# bolid-rs485-usb-sd.net
KiCad netlist of a schematic drawn in Altium Designer
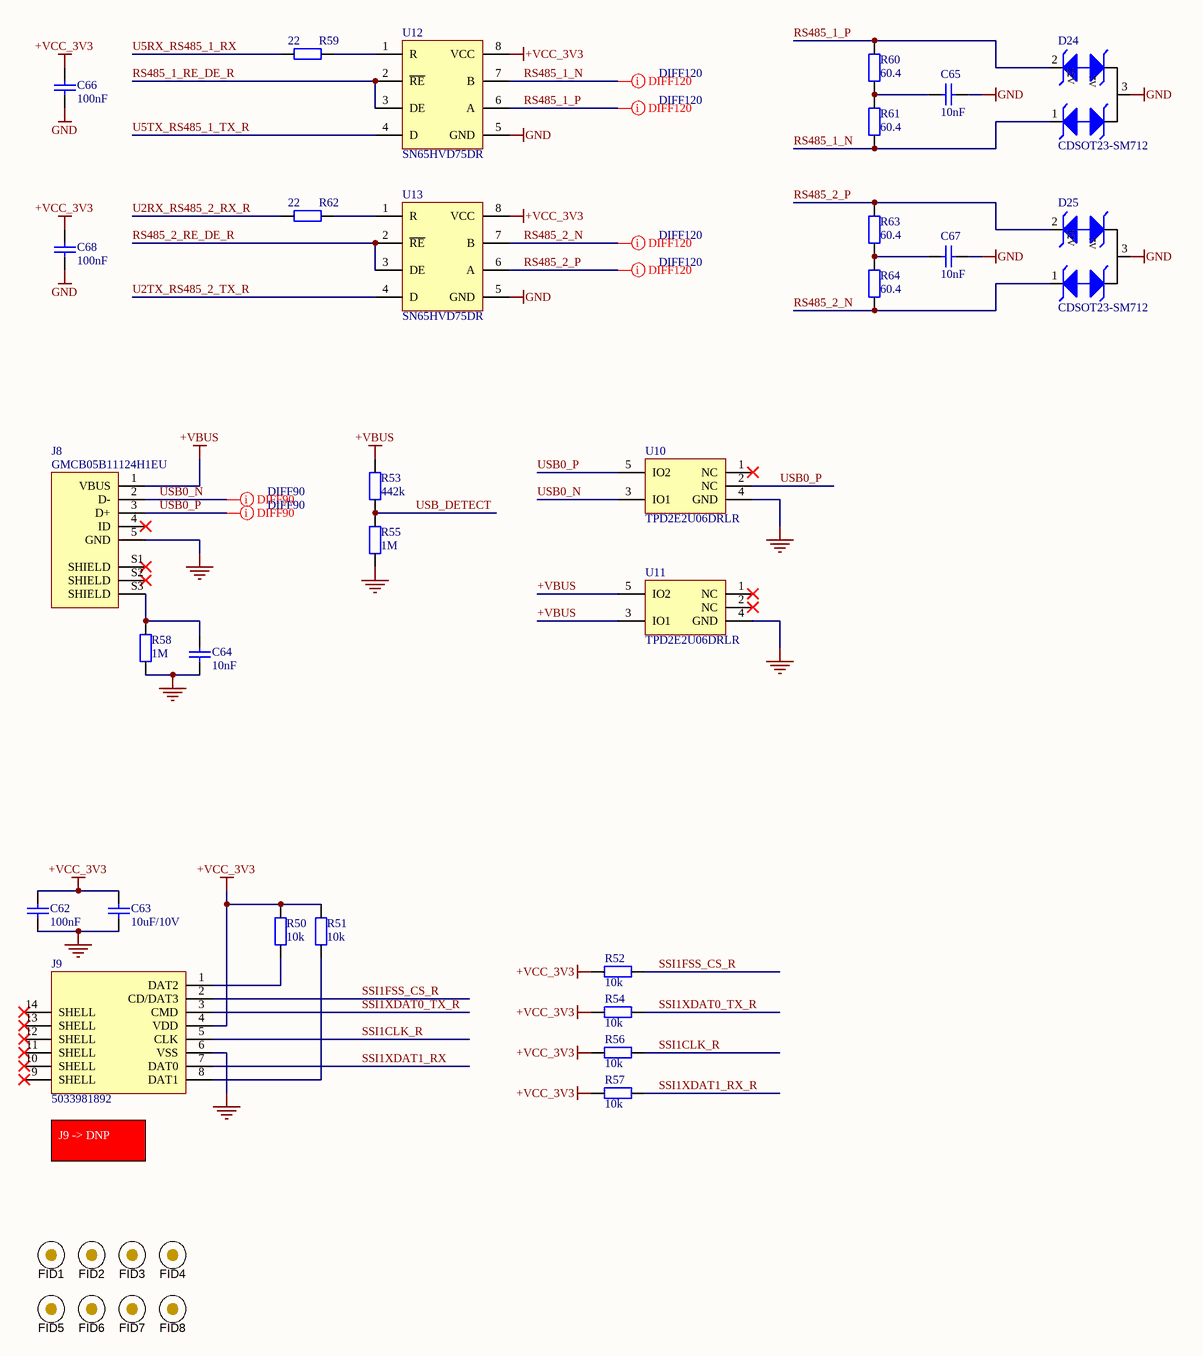
[diagram p0: bolid-rs485-usb-sd.SchDoc]

(export (version "E")
  (design (tool "Eeschema 10.0.6"))
  (components
    (comp (ref "C62")
      (value "GRM155R71H104KE14D")
      (footprint "C0402-CAPC100X50X55L22 - Tayio Yuden TDK")
      (description "MLCC 0402 (1005) 100nF 10% 50V X7R")
      (fields
        (field (name "MANUFACTURER") "Murata Electronics")
        (field (name "TOLERANCE") "10 %")
        (field (name "VALUE DISPLAYED") "100nF")
      )
      (libsource (lib "capacitors2") (part "GRM155R71H104KE14D"))
    )
    (comp (ref "C63")
      (value "GRM21BR71A106KA73K")
      (footprint "C0805-CAPC200X125X135L50N - Taiyo YudenN")
      (description "MLCC 0805 (2012) 10uF 10% 10V X7R")
      (fields
        (field (name "MANUFACTURER") "Murata Electronics")
        (field (name "TOLERANCE") "10 %")
        (field (name "VALUE DISPLAYED") "10uF/10V")
      )
      (libsource (lib "capacitors2") (part "GRM21BR71A106KA73K"))
    )
    (comp (ref "C64")
      (value "GCM155R71H103KA55D")
      (footprint "C0402-CAPC100X50X55L22 - Tayio Yuden TDK")
      (description "MLCC 0402 (1005) 10nF 10% 50V X7R")
      (fields
        (field (name "MANUFACTURER") "Murata Electronics")
        (field (name "TOLERANCE") "10 %")
        (field (name "VALUE DISPLAYED") "10nF")
      )
      (libsource (lib "capacitors2") (part "GCM155R71H103KA55D"))
    )
    (comp (ref "C65")
      (value "GCM155R71H103KA55D")
      (footprint "C0402-CAPC100X50X55L22 - Tayio Yuden TDK")
      (description "MLCC 0402 (1005) 10nF 10% 50V X7R")
      (fields
        (field (name "MANUFACTURER") "Murata Electronics")
        (field (name "TOLERANCE") "10 %")
        (field (name "VALUE DISPLAYED") "10nF")
      )
      (libsource (lib "capacitors2") (part "GCM155R71H103KA55D"))
    )
    (comp (ref "C66")
      (value "GRM155R71H104KE14D")
      (footprint "C0402-CAPC100X50X55L22 - Tayio Yuden TDK")
      (description "MLCC 0402 (1005) 100nF 10% 50V X7R")
      (fields
        (field (name "MANUFACTURER") "Murata Electronics")
        (field (name "TOLERANCE") "10 %")
        (field (name "VALUE DISPLAYED") "100nF")
      )
      (libsource (lib "capacitors2") (part "GRM155R71H104KE14D"))
    )
    (comp (ref "C67")
      (value "GCM155R71H103KA55D")
      (footprint "C0402-CAPC100X50X55L22 - Tayio Yuden TDK")
      (description "MLCC 0402 (1005) 10nF 10% 50V X7R")
      (fields
        (field (name "MANUFACTURER") "Murata Electronics")
        (field (name "TOLERANCE") "10 %")
        (field (name "VALUE DISPLAYED") "10nF")
      )
      (libsource (lib "capacitors2") (part "GCM155R71H103KA55D"))
    )
    (comp (ref "C68")
      (value "GRM155R71H104KE14D")
      (footprint "C0402-CAPC100X50X55L22 - Tayio Yuden TDK")
      (description "MLCC 0402 (1005) 100nF 10% 50V X7R")
      (fields
        (field (name "MANUFACTURER") "Murata Electronics")
        (field (name "TOLERANCE") "10 %")
        (field (name "VALUE DISPLAYED") "100nF")
      )
      (libsource (lib "capacitors2") (part "GRM155R71H104KE14D"))
    )
    (comp (ref "D24")
      (value "CDSOT23-SM712")
      (footprint "Bourns SOT-23-3L SOT23-3P95_229X117L49X40N")
      (description "TVS DIODE 7VWM/12VWM SOT23")
      (fields (field (name "MANUFACTURER") "Bourns"))
      (libsource (lib "semiconductors2") (part "CDSOT23-SM712"))
    )
    (comp (ref "D25")
      (value "CDSOT23-SM712")
      (footprint "Bourns SOT-23-3L SOT23-3P95_229X117L49X40N")
      (description "TVS DIODE 7VWM/12VWM SOT23")
      (fields (field (name "MANUFACTURER") "Bourns"))
      (libsource (lib "semiconductors2") (part "CDSOT23-SM712"))
    )
    (comp (ref "FID1")
      (value "Fiducial")
      (footprint "Fiducial10-20")
      (description "Fiducial mark on PCB")
      (libsource (lib "hardware2") (part "Fiducial"))
    )
    (comp (ref "FID2")
      (value "Fiducial")
      (footprint "Fiducial10-20")
      (description "Fiducial mark on PCB")
      (libsource (lib "hardware2") (part "Fiducial"))
    )
    (comp (ref "FID3")
      (value "Fiducial")
      (footprint "Fiducial10-20")
      (description "Fiducial mark on PCB")
      (libsource (lib "hardware2") (part "Fiducial"))
    )
    (comp (ref "FID4")
      (value "Fiducial")
      (footprint "Fiducial10-20")
      (description "Fiducial mark on PCB")
      (libsource (lib "hardware2") (part "Fiducial"))
    )
    (comp (ref "FID5")
      (value "Fiducial")
      (footprint "Fiducial10-20")
      (description "Fiducial mark on PCB")
      (libsource (lib "hardware2") (part "Fiducial"))
    )
    (comp (ref "FID6")
      (value "Fiducial")
      (footprint "Fiducial10-20")
      (description "Fiducial mark on PCB")
      (libsource (lib "hardware2") (part "Fiducial"))
    )
    (comp (ref "FID7")
      (value "Fiducial")
      (footprint "Fiducial10-20")
      (description "Fiducial mark on PCB")
      (libsource (lib "hardware2") (part "Fiducial"))
    )
    (comp (ref "FID8")
      (value "Fiducial")
      (footprint "Fiducial10-20")
      (description "Fiducial mark on PCB")
      (libsource (lib "hardware2") (part "Fiducial"))
    )
    (comp (ref "J8")
      (value "GMCB05B11124H1EU")
      (footprint "AMPHENOL-GMCB05B11124H1EU")
      (description "Micro USB 2.0 Type B Receptacle Vertical SMT Shell Dip Length 1.7mm, Tape and Reel Packagin")
      (fields (field (name "MANUFACTURER") "Amphenol"))
      (libsource (lib "connectors2") (part "GMCB05B11124H1EU"))
    )
    (comp (ref "J9")
      (value "5033981892")
      (footprint "MOLEX MICROSD 5033981892")
      (fields (field (name "MANUFACTURER") "Molex"))
      (libsource (lib "connectors2") (part "5033981892"))
    )
    (comp (ref "R50")
      (value "10k")
      (footprint "R0402-RESC100X50X40L22N")
      (description "RES 0402 (1005) 10.0k 1% 0.0625W 50V Thick Film")
      (fields
        (field (name "MANUFACTURER") "Yageo")
        (field (name "MANUFACTURER PART NUMBER") "RC0402FR-0710KL")
      )
      (libsource (lib "") (part "RC0402FR-0710KL_1"))
    )
    (comp (ref "R51")
      (value "10k")
      (footprint "R0402-RESC100X50X40L22N")
      (description "RES 0402 (1005) 10.0k 1% 0.0625W 50V Thick Film")
      (fields
        (field (name "MANUFACTURER") "Yageo")
        (field (name "MANUFACTURER PART NUMBER") "RC0402FR-0710KL")
      )
      (libsource (lib "") (part "RC0402FR-0710KL_1"))
    )
    (comp (ref "R52")
      (value "10k")
      (footprint "R0402-RESC100X50X40L22N")
      (description "RES 0402 (1005) 10.0k 1% 0.0625W 50V Thick Film")
      (fields
        (field (name "MANUFACTURER") "Yageo")
        (field (name "MANUFACTURER PART NUMBER") "RC0402FR-0710KL")
      )
      (libsource (lib "resistors2") (part "RC0402FR-0710KL"))
    )
    (comp (ref "R53")
      (value "442k")
      (footprint "R0402-RESC100X50X40L22N")
      (description "RES 0402 (1005) 442.0k 1% 0.100W 50V Thick Film")
      (fields
        (field (name "MANUFACTURER") "Panasonic")
        (field (name "MANUFACTURER PART NUMBER") "ERJ-2RKF4423X")
      )
      (libsource (lib "resistors2") (part "ERJ-2RKF4423X"))
    )
    (comp (ref "R54")
      (value "10k")
      (footprint "R0402-RESC100X50X40L22N")
      (description "RES 0402 (1005) 10.0k 1% 0.0625W 50V Thick Film")
      (fields
        (field (name "MANUFACTURER") "Yageo")
        (field (name "MANUFACTURER PART NUMBER") "RC0402FR-0710KL")
      )
      (libsource (lib "resistors2") (part "RC0402FR-0710KL"))
    )
    (comp (ref "R55")
      (value "1M")
      (footprint "R0402-RESC100X50X40L22N")
      (description "RES 0402 (1005) 1.00M 1% 0.0625W 50V Thick Film")
      (fields
        (field (name "MANUFACTURER") "YAGEO")
        (field (name "MANUFACTURER PART NUMBER") "AC0402FR-071ML")
      )
      (libsource (lib "resistors2") (part "AC0402FR-071ML"))
    )
    (comp (ref "R56")
      (value "10k")
      (footprint "R0402-RESC100X50X40L22N")
      (description "RES 0402 (1005) 10.0k 1% 0.0625W 50V Thick Film")
      (fields
        (field (name "MANUFACTURER") "Yageo")
        (field (name "MANUFACTURER PART NUMBER") "RC0402FR-0710KL")
      )
      (libsource (lib "resistors2") (part "RC0402FR-0710KL"))
    )
    (comp (ref "R57")
      (value "10k")
      (footprint "R0402-RESC100X50X40L22N")
      (description "RES 0402 (1005) 10.0k 1% 0.0625W 50V Thick Film")
      (fields
        (field (name "MANUFACTURER") "Yageo")
        (field (name "MANUFACTURER PART NUMBER") "RC0402FR-0710KL")
      )
      (libsource (lib "resistors2") (part "RC0402FR-0710KL"))
    )
    (comp (ref "R58")
      (value "1M")
      (footprint "R0402-RESC100X50X40L22N")
      (description "RES 0402 (1005) 1.00M 1% 0.0625W 50V Thick Film")
      (fields
        (field (name "MANUFACTURER") "YAGEO")
        (field (name "MANUFACTURER PART NUMBER") "AC0402FR-071ML")
      )
      (libsource (lib "resistors2") (part "AC0402FR-071ML"))
    )
    (comp (ref "R59")
      (value "22")
      (footprint "R0402-RESC100X50X40L22N")
      (description "RES 0402 (1005) 22.0 ohm 1% 0.0625W 50V Thick Film")
      (fields
        (field (name "MANUFACTURER") "Yageo")
        (field (name "MANUFACTURER PART NUMBER") "RC0402FR-1322RL")
      )
      (libsource (lib "resistors2") (part "RC0402FR-1322RL"))
    )
    (comp (ref "R60")
      (value "60.4")
      (footprint "R0603-RESC160X80X55L30N")
      (description "RES 0603 (1608) 60.4 ohm 1% 0.100W 75V Thick Film")
      (fields
        (field (name "MANUFACTURER") "Yageo")
        (field (name "MANUFACTURER PART NUMBER") "RC0603FR-0760R4L")
      )
      (libsource (lib "resistors2") (part "RC0603FR-0760R4L"))
    )
    (comp (ref "R61")
      (value "60.4")
      (footprint "R0603-RESC160X80X55L30N")
      (description "RES 0603 (1608) 60.4 ohm 1% 0.100W 75V Thick Film")
      (fields
        (field (name "MANUFACTURER") "Yageo")
        (field (name "MANUFACTURER PART NUMBER") "RC0603FR-0760R4L")
      )
      (libsource (lib "resistors2") (part "RC0603FR-0760R4L"))
    )
    (comp (ref "R62")
      (value "22")
      (footprint "R0402-RESC100X50X40L22N")
      (description "RES 0402 (1005) 22.0 ohm 1% 0.0625W 50V Thick Film")
      (fields
        (field (name "MANUFACTURER") "Yageo")
        (field (name "MANUFACTURER PART NUMBER") "RC0402FR-1322RL")
      )
      (libsource (lib "resistors2") (part "RC0402FR-1322RL"))
    )
    (comp (ref "R63")
      (value "60.4")
      (footprint "R0603-RESC160X80X55L30N")
      (description "RES 0603 (1608) 60.4 ohm 1% 0.100W 75V Thick Film")
      (fields
        (field (name "MANUFACTURER") "Yageo")
        (field (name "MANUFACTURER PART NUMBER") "RC0603FR-0760R4L")
      )
      (libsource (lib "resistors2") (part "RC0603FR-0760R4L"))
    )
    (comp (ref "R64")
      (value "60.4")
      (footprint "R0603-RESC160X80X55L30N")
      (description "RES 0603 (1608) 60.4 ohm 1% 0.100W 75V Thick Film")
      (fields
        (field (name "MANUFACTURER") "Yageo")
        (field (name "MANUFACTURER PART NUMBER") "RC0603FR-0760R4L")
      )
      (libsource (lib "resistors2") (part "RC0603FR-0760R4L"))
    )
    (comp (ref "U10")
      (value "TPD2E2U06DRLR")
      (footprint "TI SOT-5X3 DRL0005A SOTFL50P160X60-5N")
      (description "TVS DIODE 5.5VWM 12.4VC 5SOT")
      (fields (field (name "MANUFACTURER") "Texas Instruments"))
      (libsource (lib "semiconductors2") (part "TPD2E2U06DRLR"))
    )
    (comp (ref "U11")
      (value "TPD2E2U06DRLR")
      (footprint "TI SOT-5X3 DRL0005A SOTFL50P160X60-5N")
      (description "TVS DIODE 5.5VWM 12.4VC 5SOT")
      (fields (field (name "MANUFACTURER") "Texas Instruments"))
      (libsource (lib "semiconductors2") (part "TPD2E2U06DRLR"))
    )
    (comp (ref "U12")
      (value "SN65HVD75DR")
      (footprint "TI SOIC8 D0008A SOIC8P127_490X599X175L84X41N")
      (description "IC TXRX RS485 3.3V LP 8SOIC")
      (fields (field (name "MANUFACTURER") "Texas Instruments"))
      (libsource (lib "ics2") (part "SN65HVD75DR"))
    )
    (comp (ref "U13")
      (value "SN65HVD75DR")
      (footprint "TI SOIC8 D0008A SOIC8P127_490X599X175L84X41N")
      (description "IC TXRX RS485 3.3V LP 8SOIC")
      (fields (field (name "MANUFACTURER") "Texas Instruments"))
      (libsource (lib "ics2") (part "SN65HVD75DR"))
    )
  )
  (nets
    (net (code "1") (name "+VBUS") (class "Default")
      (node (ref "J8") (pin "1") (pinfunction "VBUS_1") (pintype "power_in"))
      (node (ref "R53") (pin "2") (pinfunction "2_2") (pintype "passive"))
      (node (ref "U11") (pin "3") (pinfunction "IO1_3") (pintype "passive"))
      (node (ref "U11") (pin "5") (pinfunction "IO2_5") (pintype "passive"))
    )
    (net (code "2") (name "+VCC_3V3") (class "Default")
      (node (ref "C62") (pin "2") (pinfunction "2_2") (pintype "passive"))
      (node (ref "C63") (pin "1") (pinfunction "1_1") (pintype "passive"))
      (node (ref "C66") (pin "1") (pinfunction "1_1") (pintype "passive"))
      (node (ref "C68") (pin "1") (pinfunction "1_1") (pintype "passive"))
      (node (ref "J9") (pin "4") (pinfunction "VDD_4") (pintype "passive"))
      (node (ref "R50") (pin "1") (pinfunction "1_1") (pintype "passive"))
      (node (ref "R51") (pin "1") (pinfunction "1_1") (pintype "passive"))
      (node (ref "R52") (pin "1") (pinfunction "1_1") (pintype "passive"))
      (node (ref "R54") (pin "1") (pinfunction "1_1") (pintype "passive"))
      (node (ref "R56") (pin "1") (pinfunction "1_1") (pintype "passive"))
      (node (ref "R57") (pin "1") (pinfunction "1_1") (pintype "passive"))
      (node (ref "U12") (pin "8") (pinfunction "VCC_8") (pintype "passive"))
      (node (ref "U13") (pin "8") (pinfunction "VCC_8") (pintype "passive"))
    )
    (net (code "3") (name "/RS485_1_N") (class "Default")
      (node (ref "D24") (pin "1") (pinfunction "1_1") (pintype "passive"))
      (node (ref "R61") (pin "1") (pinfunction "1_1") (pintype "passive"))
      (node (ref "U12") (pin "7") (pinfunction "B_7") (pintype "passive"))
    )
    (net (code "4") (name "/RS485_1_P") (class "Default")
      (node (ref "D24") (pin "2") (pinfunction "2_2") (pintype "passive"))
      (node (ref "R60") (pin "2") (pinfunction "2_2") (pintype "passive"))
      (node (ref "U12") (pin "6") (pinfunction "A_6") (pintype "passive"))
    )
    (net (code "5") (name "/RS485_1_RE_DE_R") (class "Default")
      (node (ref "U12") (pin "2") (pinfunction "~{RE}_2") (pintype "passive"))
      (node (ref "U12") (pin "3") (pinfunction "DE_3") (pintype "passive"))
    )
    (net (code "6") (name "/RS485_2_N") (class "Default")
      (node (ref "D25") (pin "1") (pinfunction "1_1") (pintype "passive"))
      (node (ref "R64") (pin "1") (pinfunction "1_1") (pintype "passive"))
      (node (ref "U13") (pin "7") (pinfunction "B_7") (pintype "passive"))
    )
    (net (code "7") (name "/RS485_2_P") (class "Default")
      (node (ref "D25") (pin "2") (pinfunction "2_2") (pintype "passive"))
      (node (ref "R63") (pin "2") (pinfunction "2_2") (pintype "passive"))
      (node (ref "U13") (pin "6") (pinfunction "A_6") (pintype "passive"))
    )
    (net (code "8") (name "/RS485_2_RE_DE_R") (class "Default")
      (node (ref "U13") (pin "2") (pinfunction "~{RE}_2") (pintype "passive"))
      (node (ref "U13") (pin "3") (pinfunction "DE_3") (pintype "passive"))
    )
    (net (code "9") (name "/SSI1CLK_R") (class "Default")
      (node (ref "J9") (pin "5") (pinfunction "CLK_5") (pintype "passive"))
      (node (ref "R56") (pin "2") (pinfunction "2_2") (pintype "passive"))
    )
    (net (code "10") (name "/SSI1FSS_CS_R") (class "Default")
      (node (ref "J9") (pin "2") (pinfunction "CD/DAT3_2") (pintype "passive"))
      (node (ref "R52") (pin "2") (pinfunction "2_2") (pintype "passive"))
    )
    (net (code "11") (name "/SSI1XDAT0_TX_R") (class "Default")
      (node (ref "J9") (pin "3") (pinfunction "CMD_3") (pintype "passive"))
      (node (ref "R54") (pin "2") (pinfunction "2_2") (pintype "passive"))
    )
    (net (code "12") (name "/SSI1XDAT1_RX") (class "Default")
      (node (ref "J9") (pin "7") (pinfunction "DAT0_7") (pintype "passive"))
    )
    (net (code "13") (name "/SSI1XDAT1_RX_R") (class "Default")
      (node (ref "R57") (pin "2") (pinfunction "2_2") (pintype "passive"))
    )
    (net (code "14") (name "/U2RX_RS485_2_RX_R") (class "Default")
      (node (ref "R62") (pin "1") (pinfunction "1_1") (pintype "passive"))
    )
    (net (code "15") (name "/U2TX_RS485_2_TX_R") (class "Default")
      (node (ref "U13") (pin "4") (pinfunction "D_4") (pintype "passive"))
    )
    (net (code "16") (name "/U5RX_RS485_1_RX") (class "Default")
      (node (ref "R59") (pin "1") (pinfunction "1_1") (pintype "passive"))
    )
    (net (code "17") (name "/U5TX_RS485_1_TX_R") (class "Default")
      (node (ref "U12") (pin "4") (pinfunction "D_4") (pintype "passive"))
    )
    (net (code "18") (name "/USB0_N") (class "Default")
      (node (ref "J8") (pin "2") (pinfunction "D-_2") (pintype "passive"))
      (node (ref "U10") (pin "3") (pinfunction "IO1_3") (pintype "passive"))
    )
    (net (code "19") (name "/USB0_P") (class "Default")
      (node (ref "J8") (pin "3") (pinfunction "D+_3") (pintype "passive"))
      (node (ref "U10") (pin "2") (pinfunction "NC_2") (pintype "passive"))
      (node (ref "U10") (pin "5") (pinfunction "IO2_5") (pintype "passive"))
    )
    (net (code "20") (name "/USB_DETECT") (class "Default")
      (node (ref "R53") (pin "1") (pinfunction "1_1") (pintype "passive"))
      (node (ref "R55") (pin "2") (pinfunction "2_2") (pintype "passive"))
    )
    (net (code "21") (name "GND") (class "Default")
      (node (ref "C62") (pin "1") (pinfunction "1_1") (pintype "passive"))
      (node (ref "C63") (pin "2") (pinfunction "2_2") (pintype "passive"))
      (node (ref "C64") (pin "1") (pinfunction "1_1") (pintype "passive"))
      (node (ref "C65") (pin "2") (pinfunction "2_2") (pintype "passive"))
      (node (ref "C66") (pin "2") (pinfunction "2_2") (pintype "passive"))
      (node (ref "C67") (pin "2") (pinfunction "2_2") (pintype "passive"))
      (node (ref "C68") (pin "2") (pinfunction "2_2") (pintype "passive"))
      (node (ref "D24") (pin "3") (pinfunction "3_3") (pintype "passive"))
      (node (ref "D25") (pin "3") (pinfunction "3_3") (pintype "passive"))
      (node (ref "J8") (pin "5") (pinfunction "GND_5") (pintype "power_in"))
      (node (ref "J9") (pin "6") (pinfunction "VSS_6") (pintype "passive"))
      (node (ref "R55") (pin "1") (pinfunction "1_1") (pintype "passive"))
      (node (ref "R58") (pin "1") (pinfunction "1_1") (pintype "passive"))
      (node (ref "U10") (pin "4") (pinfunction "GND_4") (pintype "passive"))
      (node (ref "U11") (pin "4") (pinfunction "GND_4") (pintype "passive"))
      (node (ref "U12") (pin "5") (pinfunction "GND_5") (pintype "passive"))
      (node (ref "U13") (pin "5") (pinfunction "GND_5") (pintype "passive"))
    )
    (net (code "22") (name "Net-(C64-Pad2)") (class "Default")
      (node (ref "C64") (pin "2") (pinfunction "2_2") (pintype "passive"))
      (node (ref "J8") (pin "S3") (pinfunction "SHIELD_S3") (pintype "passive"))
      (node (ref "R58") (pin "2") (pinfunction "2_2") (pintype "passive"))
    )
    (net (code "23") (name "Net-(C65-Pad1)") (class "Default")
      (node (ref "C65") (pin "1") (pinfunction "1_1") (pintype "passive"))
      (node (ref "R60") (pin "1") (pinfunction "1_1") (pintype "passive"))
      (node (ref "R61") (pin "2") (pinfunction "2_2") (pintype "passive"))
    )
    (net (code "24") (name "Net-(C67-Pad1)") (class "Default")
      (node (ref "C67") (pin "1") (pinfunction "1_1") (pintype "passive"))
      (node (ref "R63") (pin "1") (pinfunction "1_1") (pintype "passive"))
      (node (ref "R64") (pin "2") (pinfunction "2_2") (pintype "passive"))
    )
    (net (code "25") (name "Net-(J9-DAT1)") (class "Default")
      (node (ref "J9") (pin "8") (pinfunction "DAT1_8") (pintype "passive"))
      (node (ref "R51") (pin "2") (pinfunction "2_2") (pintype "passive"))
    )
    (net (code "26") (name "Net-(J9-DAT2)") (class "Default")
      (node (ref "J9") (pin "1") (pinfunction "DAT2_1") (pintype "passive"))
      (node (ref "R50") (pin "2") (pinfunction "2_2") (pintype "passive"))
    )
    (net (code "27") (name "Net-(U12-R)") (class "Default")
      (node (ref "R59") (pin "2") (pinfunction "2_2") (pintype "passive"))
      (node (ref "U12") (pin "1") (pinfunction "R_1") (pintype "passive"))
    )
    (net (code "28") (name "Net-(U13-R)") (class "Default")
      (node (ref "R62") (pin "2") (pinfunction "2_2") (pintype "passive"))
      (node (ref "U13") (pin "1") (pinfunction "R_1") (pintype "passive"))
    )
    (net (code "29") (name "unconnected-(FID1-PadX)") (class "Default")
      (node (ref "FID1") (pin "X") (pinfunction "X_X") (pintype "passive"))
    )
    (net (code "30") (name "unconnected-(FID2-PadX)") (class "Default")
      (node (ref "FID2") (pin "X") (pinfunction "X_X") (pintype "passive"))
    )
    (net (code "31") (name "unconnected-(FID3-PadX)") (class "Default")
      (node (ref "FID3") (pin "X") (pinfunction "X_X") (pintype "passive"))
    )
    (net (code "32") (name "unconnected-(FID4-PadX)") (class "Default")
      (node (ref "FID4") (pin "X") (pinfunction "X_X") (pintype "passive"))
    )
    (net (code "33") (name "unconnected-(FID5-PadX)") (class "Default")
      (node (ref "FID5") (pin "X") (pinfunction "X_X") (pintype "passive"))
    )
    (net (code "34") (name "unconnected-(FID6-PadX)") (class "Default")
      (node (ref "FID6") (pin "X") (pinfunction "X_X") (pintype "passive"))
    )
    (net (code "35") (name "unconnected-(FID7-PadX)") (class "Default")
      (node (ref "FID7") (pin "X") (pinfunction "X_X") (pintype "passive"))
    )
    (net (code "36") (name "unconnected-(FID8-PadX)") (class "Default")
      (node (ref "FID8") (pin "X") (pinfunction "X_X") (pintype "passive"))
    )
    (net (code "37") (name "unconnected-(J8-ID-Pad4)") (class "Default")
      (node (ref "J8") (pin "4") (pinfunction "ID_4") (pintype "passive+no_connect"))
    )
    (net (code "38") (name "unconnected-(J8-SHIELD-PadS1)") (class "Default")
      (node (ref "J8") (pin "S1") (pinfunction "SHIELD_S1") (pintype "passive+no_connect"))
    )
    (net (code "39") (name "unconnected-(J8-SHIELD-PadS2)") (class "Default")
      (node (ref "J8") (pin "S2") (pinfunction "SHIELD_S2") (pintype "passive+no_connect"))
    )
    (net (code "40") (name "unconnected-(J9-SHELL-Pad9)") (class "Default")
      (node (ref "J9") (pin "9") (pinfunction "SHELL_9") (pintype "passive+no_connect"))
    )
    (net (code "41") (name "unconnected-(J9-SHELL-Pad10)") (class "Default")
      (node (ref "J9") (pin "10") (pinfunction "SHELL_10") (pintype "passive+no_connect"))
    )
    (net (code "42") (name "unconnected-(J9-SHELL-Pad11)") (class "Default")
      (node (ref "J9") (pin "11") (pinfunction "SHELL_11") (pintype "passive+no_connect"))
    )
    (net (code "43") (name "unconnected-(J9-SHELL-Pad12)") (class "Default")
      (node (ref "J9") (pin "12") (pinfunction "SHELL_12") (pintype "passive+no_connect"))
    )
    (net (code "44") (name "unconnected-(J9-SHELL-Pad13)") (class "Default")
      (node (ref "J9") (pin "13") (pinfunction "SHELL_13") (pintype "passive+no_connect"))
    )
    (net (code "45") (name "unconnected-(J9-SHELL-Pad14)") (class "Default")
      (node (ref "J9") (pin "14") (pinfunction "SHELL_14") (pintype "passive+no_connect"))
    )
    (net (code "46") (name "unconnected-(U10-NC-Pad1)") (class "Default")
      (node (ref "U10") (pin "1") (pinfunction "NC_1") (pintype "passive+no_connect"))
    )
    (net (code "47") (name "unconnected-(U11-NC-Pad1)") (class "Default")
      (node (ref "U11") (pin "1") (pinfunction "NC_1") (pintype "passive+no_connect"))
    )
    (net (code "48") (name "unconnected-(U11-NC-Pad2)") (class "Default")
      (node (ref "U11") (pin "2") (pinfunction "NC_2") (pintype "passive+no_connect"))
    )
  )
)
